# BurnBabyBurn.net
KiCad netlist of a schematic drawn in EAGLE
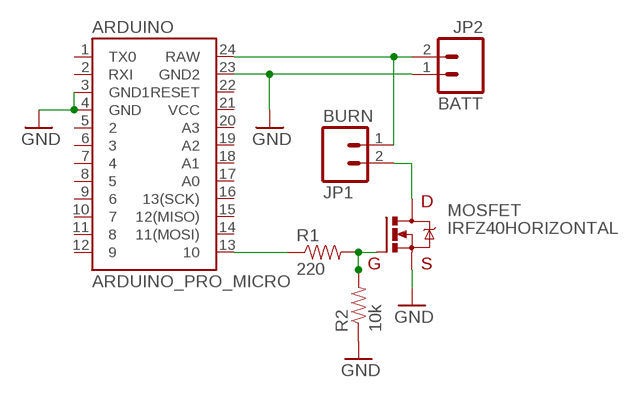
[diagram p0: schematic, sheet 1]

(export (version "E")
  (design (tool "Eeschema 10.0.6"))
  (components
    (comp (ref "ARDUINO")
      (value "ARDUINO_PRO_MICRO")
      (footprint "eagle-import:ARDUINO_PRO_MICRO")
      (libsource (lib "eagle-import") (part "ARDUINO_PRO_MICRO"))
    )
    (comp (ref "JP1")
      (value "BURN")
      (footprint "eagle-import:SCREWTERMINAL-3.5MM-2")
      (libsource (lib "eagle-import") (part "M023.5MM"))
    )
    (comp (ref "JP2")
      (value "BATT")
      (footprint "eagle-import:SCREWTERMINAL-3.5MM-2")
      (libsource (lib "eagle-import") (part "M023.5MM"))
    )
    (comp (ref "MOSFET")
      (value "IRFZ40HORIZONTAL")
      (footprint "eagle-import:TO220")
      (libsource (lib "eagle-import") (part "IRFZ40HORIZONTAL"))
    )
    (comp (ref "R1")
      (value "220")
      (footprint "eagle-import:AXIAL-0.3EZ")
      (libsource (lib "eagle-import") (part "RESISTOREZ"))
    )
    (comp (ref "R2")
      (value "10k")
      (footprint "eagle-import:AXIAL-0.3EZ")
      (libsource (lib "eagle-import") (part "RESISTOREZ"))
    )
  )
  (nets
    (net (code "1") (name "GND") (class "Default")
      (node (ref "ARDUINO") (pin "23") (pinfunction "GND2_23") (pintype "bidirectional"))
      (node (ref "ARDUINO") (pin "3") (pinfunction "GND1_3") (pintype "bidirectional"))
      (node (ref "ARDUINO") (pin "4") (pinfunction "GND_4") (pintype "bidirectional"))
      (node (ref "JP2") (pin "1") (pinfunction "1_1") (pintype "passive"))
      (node (ref "MOSFET") (pin "3") (pinfunction "S_3") (pintype "passive"))
      (node (ref "R2") (pin "P$1") (pinfunction "1_P$1") (pintype "passive"))
    )
    (net (code "2") (name "Net-(ARDUINO-10)") (class "Default")
      (node (ref "ARDUINO") (pin "13") (pinfunction "10_13") (pintype "bidirectional"))
      (node (ref "R1") (pin "P$1") (pinfunction "1_P$1") (pintype "passive"))
    )
    (net (code "3") (name "Net-(ARDUINO-RAW)") (class "Default")
      (node (ref "ARDUINO") (pin "24") (pinfunction "RAW_24") (pintype "bidirectional"))
      (node (ref "JP1") (pin "1") (pinfunction "1_1") (pintype "passive"))
      (node (ref "JP2") (pin "2") (pinfunction "2_2") (pintype "passive"))
    )
    (net (code "4") (name "Net-(MOSFET-D)") (class "Default")
      (node (ref "JP1") (pin "2") (pinfunction "2_2") (pintype "passive"))
      (node (ref "MOSFET") (pin "2") (pinfunction "D_2") (pintype "passive"))
    )
    (net (code "5") (name "Net-(MOSFET-G)") (class "Default")
      (node (ref "MOSFET") (pin "1") (pinfunction "G_1") (pintype "passive"))
      (node (ref "R1") (pin "P$2") (pinfunction "2_P$2") (pintype "passive"))
      (node (ref "R2") (pin "P$2") (pinfunction "2_P$2") (pintype "passive"))
    )
    (net (code "6") (name "unconnected-(ARDUINO-2-Pad5)") (class "Default")
      (node (ref "ARDUINO") (pin "5") (pinfunction "2_5") (pintype "bidirectional"))
    )
    (net (code "7") (name "unconnected-(ARDUINO-3-Pad6)") (class "Default")
      (node (ref "ARDUINO") (pin "6") (pinfunction "3_6") (pintype "bidirectional"))
    )
    (net (code "8") (name "unconnected-(ARDUINO-4-Pad7)") (class "Default")
      (node (ref "ARDUINO") (pin "7") (pinfunction "4_7") (pintype "bidirectional"))
    )
    (net (code "9") (name "unconnected-(ARDUINO-5-Pad8)") (class "Default")
      (node (ref "ARDUINO") (pin "8") (pinfunction "5_8") (pintype "bidirectional"))
    )
    (net (code "10") (name "unconnected-(ARDUINO-6-Pad9)") (class "Default")
      (node (ref "ARDUINO") (pin "9") (pinfunction "6_9") (pintype "bidirectional"))
    )
    (net (code "11") (name "unconnected-(ARDUINO-7-Pad10)") (class "Default")
      (node (ref "ARDUINO") (pin "10") (pinfunction "7_10") (pintype "bidirectional"))
    )
    (net (code "12") (name "unconnected-(ARDUINO-8-Pad11)") (class "Default")
      (node (ref "ARDUINO") (pin "11") (pinfunction "8_11") (pintype "bidirectional"))
    )
    (net (code "13") (name "unconnected-(ARDUINO-9-Pad12)") (class "Default")
      (node (ref "ARDUINO") (pin "12") (pinfunction "9_12") (pintype "bidirectional"))
    )
    (net (code "14") (name "unconnected-(ARDUINO-11(MOSI)-Pad14)") (class "Default")
      (node (ref "ARDUINO") (pin "14") (pinfunction "11(MOSI)_14") (pintype "bidirectional"))
    )
    (net (code "15") (name "unconnected-(ARDUINO-12(MISO)-Pad15)") (class "Default")
      (node (ref "ARDUINO") (pin "15") (pinfunction "12(MISO)_15") (pintype "bidirectional"))
    )
    (net (code "16") (name "unconnected-(ARDUINO-13(SCK)-Pad16)") (class "Default")
      (node (ref "ARDUINO") (pin "16") (pinfunction "13(SCK)_16") (pintype "bidirectional"))
    )
    (net (code "17") (name "unconnected-(ARDUINO-A0-Pad17)") (class "Default")
      (node (ref "ARDUINO") (pin "17") (pinfunction "A0_17") (pintype "bidirectional"))
    )
    (net (code "18") (name "unconnected-(ARDUINO-A1-Pad18)") (class "Default")
      (node (ref "ARDUINO") (pin "18") (pinfunction "A1_18") (pintype "bidirectional"))
    )
    (net (code "19") (name "unconnected-(ARDUINO-A2-Pad19)") (class "Default")
      (node (ref "ARDUINO") (pin "19") (pinfunction "A2_19") (pintype "bidirectional"))
    )
    (net (code "20") (name "unconnected-(ARDUINO-A3-Pad20)") (class "Default")
      (node (ref "ARDUINO") (pin "20") (pinfunction "A3_20") (pintype "bidirectional"))
    )
    (net (code "21") (name "unconnected-(ARDUINO-RESET-Pad22)") (class "Default")
      (node (ref "ARDUINO") (pin "22") (pinfunction "RESET_22") (pintype "bidirectional"))
    )
    (net (code "22") (name "unconnected-(ARDUINO-RXI-Pad2)") (class "Default")
      (node (ref "ARDUINO") (pin "2") (pinfunction "RXI_2") (pintype "bidirectional"))
    )
    (net (code "23") (name "unconnected-(ARDUINO-TX0-Pad1)") (class "Default")
      (node (ref "ARDUINO") (pin "1") (pinfunction "TX0_1") (pintype "bidirectional"))
    )
    (net (code "24") (name "unconnected-(ARDUINO-VCC-Pad21)") (class "Default")
      (node (ref "ARDUINO") (pin "21") (pinfunction "VCC_21") (pintype "bidirectional"))
    )
  )
)
